# PCIE.net
KiCad netlist of a schematic drawn in Altium Designer
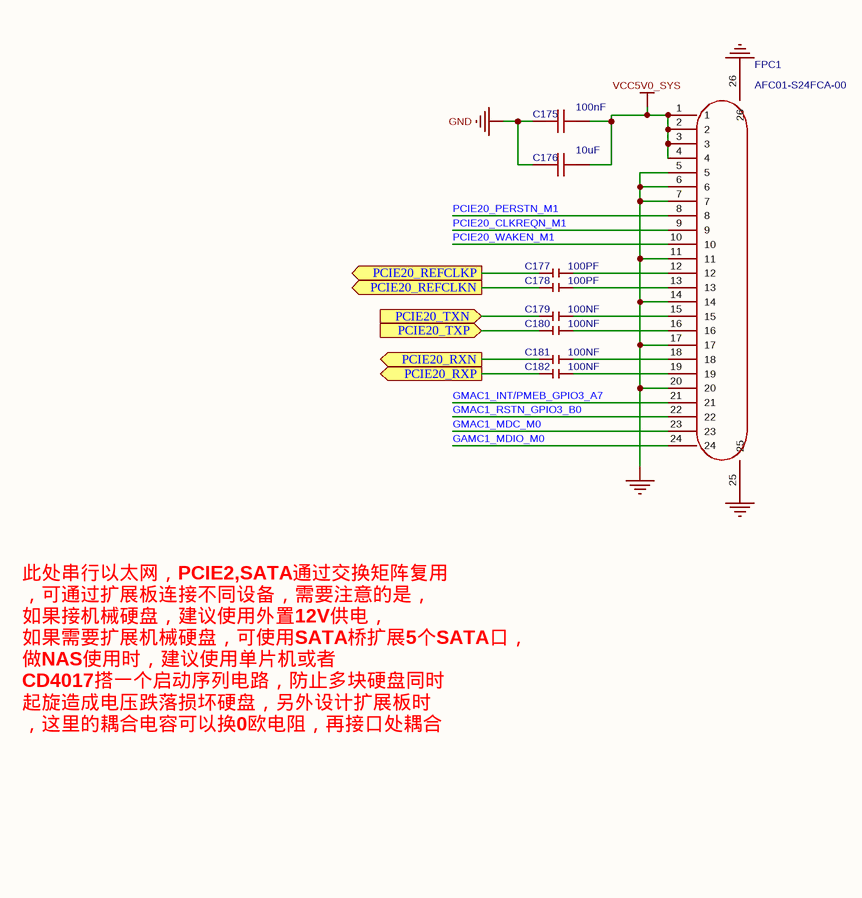
[diagram p0: PCIE.schdoc]

(export (version "E")
  (design (tool "Eeschema 10.0.6"))
  (components
    (comp (ref "C175")
      (value "100nF")
      (footprint "C0603")
      (libsource (lib "altium-import") (part "root_0_CAP_0603_"))
    )
    (comp (ref "C176")
      (value "10uF")
      (footprint "C0603")
      (libsource (lib "altium-import") (part "root_0_CAP_0603_"))
    )
    (comp (ref "C177")
      (value "100PF")
      (footprint "MYC0402")
      (description "C0402电容")
      (libsource (lib "altium-import") (part "root_0_MYC0402_"))
    )
    (comp (ref "C178")
      (value "100PF")
      (footprint "MYC0402")
      (description "C0402电容")
      (libsource (lib "altium-import") (part "root_0_MYC0402_"))
    )
    (comp (ref "C179")
      (value "100NF")
      (footprint "MYC0402")
      (description "C0402电容")
      (libsource (lib "altium-import") (part "root_0_MYC0402_"))
    )
    (comp (ref "C180")
      (value "100NF")
      (footprint "MYC0402")
      (description "C0402电容")
      (libsource (lib "altium-import") (part "root_0_MYC0402_"))
    )
    (comp (ref "C181")
      (value "100NF")
      (footprint "MYC0402")
      (description "C0402电容")
      (libsource (lib "altium-import") (part "root_0_MYC0402_"))
    )
    (comp (ref "C182")
      (value "100NF")
      (footprint "MYC0402")
      (description "C0402电容")
      (libsource (lib "altium-import") (part "root_0_MYC0402_"))
    )
    (comp (ref "FPC1")
      (value "AFC01-S24FCA-00")
      (footprint "FPC-SMD_24P-P0.50_AFC01-S24FCA-00")
      (description "锁定特性:翻盖式;触点类型:下接;触点数量:24P;间距:0.5mm;安装方式:卧贴;")
      (fields (field (name "MANUFACTURER") "JS(钜硕电子)"))
      (libsource (lib "altium-import") (part "root_0_AFC01-S24FCA-00_"))
    )
  )
  (nets
    (net (code "1") (name "/GAMC1_MDIO_M0") (class "Default")
      (node (ref "FPC1") (pin "24") (pinfunction "24_24") (pintype "passive"))
    )
    (net (code "2") (name "/GMAC1_INT{slash}PMEB_GPIO3_A7") (class "Default")
      (node (ref "FPC1") (pin "21") (pinfunction "21_21") (pintype "passive"))
    )
    (net (code "3") (name "/GMAC1_MDC_M0") (class "Default")
      (node (ref "FPC1") (pin "23") (pinfunction "23_23") (pintype "passive"))
    )
    (net (code "4") (name "/GMAC1_RSTN_GPIO3_B0") (class "Default")
      (node (ref "FPC1") (pin "22") (pinfunction "22_22") (pintype "passive"))
    )
    (net (code "5") (name "/PCIE20_CLKREQN_M1") (class "Default")
      (node (ref "FPC1") (pin "9") (pinfunction "9_9") (pintype "passive"))
    )
    (net (code "6") (name "/PCIE20_PERSTN_M1") (class "Default")
      (node (ref "FPC1") (pin "8") (pinfunction "8_8") (pintype "passive"))
    )
    (net (code "7") (name "/PCIE20_REFCLKN") (class "Default")
      (node (ref "C178") (pin "1") (pinfunction "1_1") (pintype "passive"))
    )
    (net (code "8") (name "/PCIE20_REFCLKP") (class "Default")
      (node (ref "C177") (pin "1") (pinfunction "1_1") (pintype "passive"))
    )
    (net (code "9") (name "/PCIE20_RXN") (class "Default")
      (node (ref "C181") (pin "1") (pinfunction "1_1") (pintype "passive"))
    )
    (net (code "10") (name "/PCIE20_RXP") (class "Default")
      (node (ref "C182") (pin "1") (pinfunction "1_1") (pintype "passive"))
    )
    (net (code "11") (name "/PCIE20_TXN") (class "Default")
      (node (ref "C179") (pin "1") (pinfunction "1_1") (pintype "passive"))
    )
    (net (code "12") (name "/PCIE20_TXP") (class "Default")
      (node (ref "C180") (pin "1") (pinfunction "1_1") (pintype "passive"))
    )
    (net (code "13") (name "/PCIE20_WAKEN_M1") (class "Default")
      (node (ref "FPC1") (pin "10") (pinfunction "10_10") (pintype "passive"))
    )
    (net (code "14") (name "GND") (class "Default")
      (node (ref "C175") (pin "1") (pinfunction "1_1") (pintype "passive"))
      (node (ref "C176") (pin "1") (pinfunction "1_1") (pintype "passive"))
      (node (ref "FPC1") (pin "11") (pinfunction "11_11") (pintype "passive"))
      (node (ref "FPC1") (pin "14") (pinfunction "14_14") (pintype "passive"))
      (node (ref "FPC1") (pin "17") (pinfunction "17_17") (pintype "passive"))
      (node (ref "FPC1") (pin "20") (pinfunction "20_20") (pintype "passive"))
      (node (ref "FPC1") (pin "25") (pinfunction "25_25") (pintype "passive"))
      (node (ref "FPC1") (pin "26") (pinfunction "26_26") (pintype "passive"))
      (node (ref "FPC1") (pin "5") (pinfunction "5_5") (pintype "passive"))
      (node (ref "FPC1") (pin "6") (pinfunction "6_6") (pintype "passive"))
      (node (ref "FPC1") (pin "7") (pinfunction "7_7") (pintype "passive"))
    )
    (net (code "15") (name "Net-(C177-Pad2)") (class "Default")
      (node (ref "C177") (pin "2") (pinfunction "2_2") (pintype "passive"))
      (node (ref "FPC1") (pin "12") (pinfunction "12_12") (pintype "passive"))
    )
    (net (code "16") (name "Net-(C178-Pad2)") (class "Default")
      (node (ref "C178") (pin "2") (pinfunction "2_2") (pintype "passive"))
      (node (ref "FPC1") (pin "13") (pinfunction "13_13") (pintype "passive"))
    )
    (net (code "17") (name "Net-(C179-Pad2)") (class "Default")
      (node (ref "C179") (pin "2") (pinfunction "2_2") (pintype "passive"))
      (node (ref "FPC1") (pin "15") (pinfunction "15_15") (pintype "passive"))
    )
    (net (code "18") (name "Net-(C180-Pad2)") (class "Default")
      (node (ref "C180") (pin "2") (pinfunction "2_2") (pintype "passive"))
      (node (ref "FPC1") (pin "16") (pinfunction "16_16") (pintype "passive"))
    )
    (net (code "19") (name "Net-(C181-Pad2)") (class "Default")
      (node (ref "C181") (pin "2") (pinfunction "2_2") (pintype "passive"))
      (node (ref "FPC1") (pin "18") (pinfunction "18_18") (pintype "passive"))
    )
    (net (code "20") (name "Net-(C182-Pad2)") (class "Default")
      (node (ref "C182") (pin "2") (pinfunction "2_2") (pintype "passive"))
      (node (ref "FPC1") (pin "19") (pinfunction "19_19") (pintype "passive"))
    )
    (net (code "21") (name "VCC5V0_SYS") (class "Default")
      (node (ref "C175") (pin "2") (pinfunction "2_2") (pintype "passive"))
      (node (ref "C176") (pin "2") (pinfunction "2_2") (pintype "passive"))
      (node (ref "FPC1") (pin "1") (pinfunction "1_1") (pintype "passive"))
      (node (ref "FPC1") (pin "2") (pinfunction "2_2") (pintype "passive"))
      (node (ref "FPC1") (pin "3") (pinfunction "3_3") (pintype "passive"))
      (node (ref "FPC1") (pin "4") (pinfunction "4_4") (pintype "passive"))
    )
  )
)
